# SCH_HackClub-PCB-1_2024-05-19.net
KiCad netlist of a schematic drawn in EasyEDA
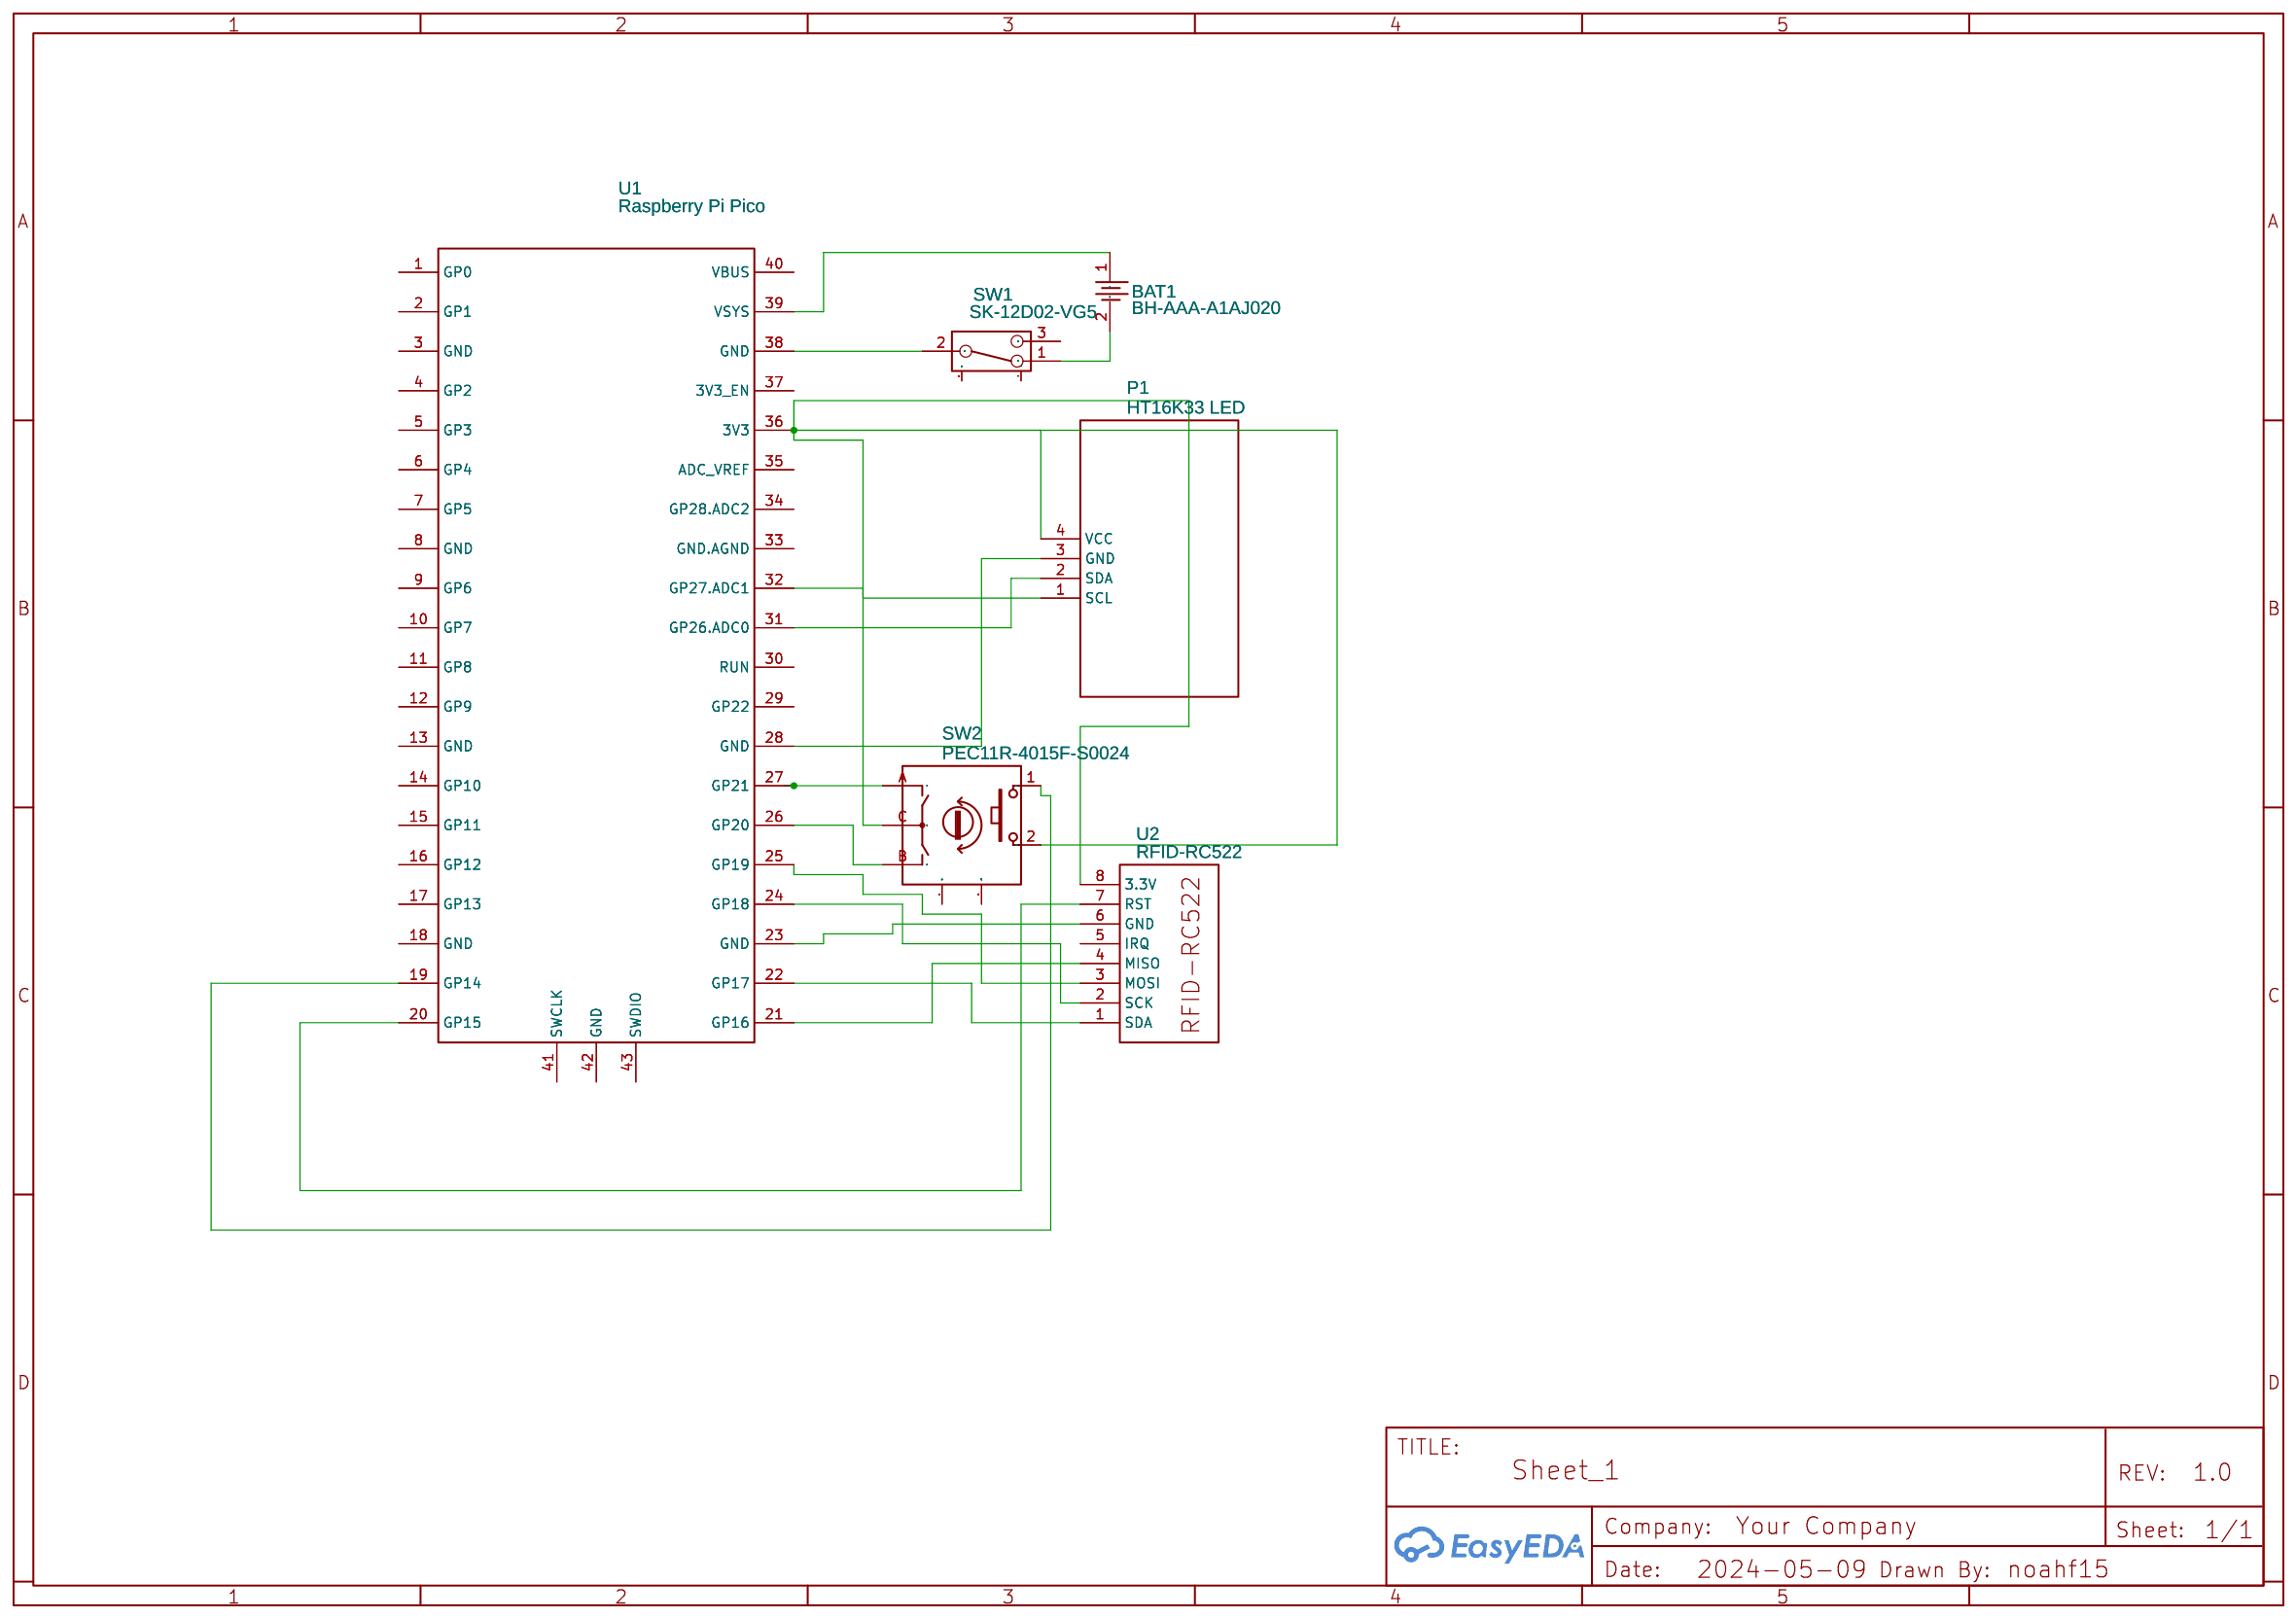
[diagram p0: schematic sheet]

(export (version "E")
  (design (tool "Eeschema 10.0.6"))
  (components
    (comp (ref "BAT1")
      (value "BH-AAA-A1AJ020")
      (fields (field (name "Manufacturer") "MYOUNG(美阳)"))
      (libsource (lib "") (part "BH-AAA-A1AJ020"))
    )
    (comp (ref "P1") (value "HT16K33 LED") (libsource (lib "") (part "HT16K33 LED")))
    (comp (ref "SW1")
      (value "SK-12D02-VG5")
      (fields (field (name "Manufacturer") "Rectangular Connectors - Contacts"))
      (libsource (lib "") (part "SK-12D02-VG5"))
    )
    (comp (ref "SW2")
      (value "PEC11R-4015F-S0024")
      (fields (field (name "Manufacturer") "BOURNS"))
      (libsource (lib "") (part "PEC11R-4015F-S0024"))
    )
    (comp (ref "U1")
      (value "Raspberry Pi Pico")
      (fields (field (name "Manufacturer") "Raspberry Pi Foundation"))
      (libsource (lib "") (part "Raspberry Pi Pico"))
    )
    (comp (ref "U2") (value "RFID-RC522") (libsource (lib "") (part "RFID-RC522")))
  )
  (nets
    (net (code "1") (name "Net-(BAT1-Pad2)") (class "Default")
      (node (ref "BAT1") (pin "2") (pinfunction "2_2") (pintype "input"))
      (node (ref "SW1") (pin "1") (pinfunction "1_1") (pintype "unspecified"))
    )
    (net (code "2") (name "Net-(P1-GND)") (class "Default")
      (node (ref "P1") (pin "3") (pinfunction "GND_3") (pintype "unspecified"))
      (node (ref "U1") (pin "28") (pinfunction "GND_28") (pintype "passive"))
    )
    (net (code "3") (name "Net-(P1-SCL)") (class "Default")
      (node (ref "P1") (pin "1") (pinfunction "SCL_1") (pintype "unspecified"))
      (node (ref "U1") (pin "32") (pinfunction "GP27.ADC1_32") (pintype "bidirectional"))
    )
    (net (code "4") (name "Net-(P1-SDA)") (class "Default")
      (node (ref "P1") (pin "2") (pinfunction "SDA_2") (pintype "unspecified"))
      (node (ref "U1") (pin "31") (pinfunction "GP26.ADC0_31") (pintype "bidirectional"))
    )
    (net (code "5") (name "Net-(P1-VCC)") (class "Default")
      (node (ref "P1") (pin "4") (pinfunction "VCC_4") (pintype "unspecified"))
      (node (ref "SW2") (pin "2") (pinfunction "2_2") (pintype "unspecified"))
      (node (ref "SW2") (pin "C") (pinfunction "C_C") (pintype "unspecified"))
      (node (ref "U1") (pin "36") (pinfunction "3V3_36") (pintype "passive"))
      (node (ref "U2") (pin "8") (pinfunction "3.3V_8") (pintype "unspecified"))
    )
    (net (code "6") (name "Net-(SW1-Pad2)") (class "Default")
      (node (ref "SW1") (pin "2") (pinfunction "2_2") (pintype "unspecified"))
      (node (ref "U1") (pin "38") (pinfunction "GND_38") (pintype "passive"))
    )
    (net (code "7") (name "Net-(U1-GP14)") (class "Default")
      (node (ref "SW2") (pin "1") (pinfunction "1_1") (pintype "unspecified"))
      (node (ref "U1") (pin "19") (pinfunction "GP14_19") (pintype "bidirectional"))
    )
    (net (code "8") (name "Net-(U1-GP15)") (class "Default")
      (node (ref "U1") (pin "20") (pinfunction "GP15_20") (pintype "bidirectional"))
      (node (ref "U2") (pin "7") (pinfunction "RST_7") (pintype "unspecified"))
    )
    (net (code "9") (name "Net-(U1-GP16)") (class "Default")
      (node (ref "U1") (pin "21") (pinfunction "GP16_21") (pintype "bidirectional"))
      (node (ref "U2") (pin "4") (pinfunction "MISO_4") (pintype "unspecified"))
    )
    (net (code "10") (name "Net-(U1-GP17)") (class "Default")
      (node (ref "U1") (pin "22") (pinfunction "GP17_22") (pintype "bidirectional"))
      (node (ref "U2") (pin "1") (pinfunction "SDA_1") (pintype "unspecified"))
    )
    (net (code "11") (name "Net-(U1-GP18)") (class "Default")
      (node (ref "U1") (pin "24") (pinfunction "GP18_24") (pintype "bidirectional"))
      (node (ref "U2") (pin "2") (pinfunction "SCK_2") (pintype "unspecified"))
    )
    (net (code "12") (name "Net-(U1-GP19)") (class "Default")
      (node (ref "U1") (pin "25") (pinfunction "GP19_25") (pintype "bidirectional"))
      (node (ref "U2") (pin "3") (pinfunction "MOSI_3") (pintype "unspecified"))
    )
    (net (code "13") (name "Net-(U1-GP20)") (class "Default")
      (node (ref "SW2") (pin "B") (pinfunction "B_B") (pintype "unspecified"))
      (node (ref "U1") (pin "26") (pinfunction "GP20_26") (pintype "bidirectional"))
    )
    (net (code "14") (name "Net-(U1-GP21)") (class "Default")
      (node (ref "SW2") (pin "A") (pinfunction "A_A") (pintype "unspecified"))
      (node (ref "U1") (pin "27") (pinfunction "GP21_27") (pintype "bidirectional"))
    )
    (net (code "15") (name "Net-(U1-VSYS)") (class "Default")
      (node (ref "BAT1") (pin "1") (pinfunction "1_1") (pintype "input"))
      (node (ref "U1") (pin "39") (pinfunction "VSYS_39") (pintype "passive"))
    )
    (net (code "16") (name "Net-(U2-GND)") (class "Default")
      (node (ref "U1") (pin "23") (pinfunction "GND_23") (pintype "passive"))
      (node (ref "U2") (pin "6") (pinfunction "GND_6") (pintype "unspecified"))
    )
    (net (code "17") (name "unconnected-(SW1-Pad3)") (class "Default")
      (node (ref "SW1") (pin "3") (pinfunction "3_3") (pintype "unspecified"))
    )
    (net (code "18") (name "unconnected-(SW1-Pad4)") (class "Default")
      (node (ref "SW1") (pin "4") (pinfunction "4_4") (pintype "unspecified"))
    )
    (net (code "19") (name "unconnected-(SW1-Pad5)") (class "Default")
      (node (ref "SW1") (pin "5") (pinfunction "5_5") (pintype "unspecified"))
    )
    (net (code "20") (name "unconnected-(SW2-PadMT1)") (class "Default")
      (node (ref "SW2") (pin "MT1") (pinfunction "MT1_MT1") (pintype "unspecified"))
    )
    (net (code "21") (name "unconnected-(SW2-PadMT2)") (class "Default")
      (node (ref "SW2") (pin "MT2") (pinfunction "MT2_MT2") (pintype "unspecified"))
    )
    (net (code "22") (name "unconnected-(U1-3V3_EN-Pad37)") (class "Default")
      (node (ref "U1") (pin "37") (pinfunction "3V3_EN_37") (pintype "input"))
    )
    (net (code "23") (name "unconnected-(U1-ADC_VREF-Pad35)") (class "Default")
      (node (ref "U1") (pin "35") (pinfunction "ADC_VREF_35") (pintype "passive"))
    )
    (net (code "24") (name "unconnected-(U1-GND-Pad3)") (class "Default")
      (node (ref "U1") (pin "3") (pinfunction "GND_3") (pintype "passive"))
    )
    (net (code "25") (name "unconnected-(U1-GND-Pad8)") (class "Default")
      (node (ref "U1") (pin "8") (pinfunction "GND_8") (pintype "passive"))
    )
    (net (code "26") (name "unconnected-(U1-GND-Pad13)") (class "Default")
      (node (ref "U1") (pin "13") (pinfunction "GND_13") (pintype "passive"))
    )
    (net (code "27") (name "unconnected-(U1-GND-Pad18)") (class "Default")
      (node (ref "U1") (pin "18") (pinfunction "GND_18") (pintype "passive"))
    )
    (net (code "28") (name "unconnected-(U1-GND-Pad42)") (class "Default")
      (node (ref "U1") (pin "42") (pinfunction "GND_42") (pintype "passive"))
    )
    (net (code "29") (name "unconnected-(U1-GND.AGND-Pad33)") (class "Default")
      (node (ref "U1") (pin "33") (pinfunction "GND.AGND_33") (pintype "passive"))
    )
    (net (code "30") (name "unconnected-(U1-GP0-Pad1)") (class "Default")
      (node (ref "U1") (pin "1") (pinfunction "GP0_1") (pintype "bidirectional"))
    )
    (net (code "31") (name "unconnected-(U1-GP1-Pad2)") (class "Default")
      (node (ref "U1") (pin "2") (pinfunction "GP1_2") (pintype "bidirectional"))
    )
    (net (code "32") (name "unconnected-(U1-GP2-Pad4)") (class "Default")
      (node (ref "U1") (pin "4") (pinfunction "GP2_4") (pintype "bidirectional"))
    )
    (net (code "33") (name "unconnected-(U1-GP3-Pad5)") (class "Default")
      (node (ref "U1") (pin "5") (pinfunction "GP3_5") (pintype "bidirectional"))
    )
    (net (code "34") (name "unconnected-(U1-GP4-Pad6)") (class "Default")
      (node (ref "U1") (pin "6") (pinfunction "GP4_6") (pintype "bidirectional"))
    )
    (net (code "35") (name "unconnected-(U1-GP5-Pad7)") (class "Default")
      (node (ref "U1") (pin "7") (pinfunction "GP5_7") (pintype "bidirectional"))
    )
    (net (code "36") (name "unconnected-(U1-GP6-Pad9)") (class "Default")
      (node (ref "U1") (pin "9") (pinfunction "GP6_9") (pintype "bidirectional"))
    )
    (net (code "37") (name "unconnected-(U1-GP7-Pad10)") (class "Default")
      (node (ref "U1") (pin "10") (pinfunction "GP7_10") (pintype "bidirectional"))
    )
    (net (code "38") (name "unconnected-(U1-GP8-Pad11)") (class "Default")
      (node (ref "U1") (pin "11") (pinfunction "GP8_11") (pintype "bidirectional"))
    )
    (net (code "39") (name "unconnected-(U1-GP9-Pad12)") (class "Default")
      (node (ref "U1") (pin "12") (pinfunction "GP9_12") (pintype "bidirectional"))
    )
    (net (code "40") (name "unconnected-(U1-GP10-Pad14)") (class "Default")
      (node (ref "U1") (pin "14") (pinfunction "GP10_14") (pintype "bidirectional"))
    )
    (net (code "41") (name "unconnected-(U1-GP11-Pad15)") (class "Default")
      (node (ref "U1") (pin "15") (pinfunction "GP11_15") (pintype "bidirectional"))
    )
    (net (code "42") (name "unconnected-(U1-GP12-Pad16)") (class "Default")
      (node (ref "U1") (pin "16") (pinfunction "GP12_16") (pintype "bidirectional"))
    )
    (net (code "43") (name "unconnected-(U1-GP13-Pad17)") (class "Default")
      (node (ref "U1") (pin "17") (pinfunction "GP13_17") (pintype "bidirectional"))
    )
    (net (code "44") (name "unconnected-(U1-GP22-Pad29)") (class "Default")
      (node (ref "U1") (pin "29") (pinfunction "GP22_29") (pintype "bidirectional"))
    )
    (net (code "45") (name "unconnected-(U1-GP28.ADC2-Pad34)") (class "Default")
      (node (ref "U1") (pin "34") (pinfunction "GP28.ADC2_34") (pintype "bidirectional"))
    )
    (net (code "46") (name "unconnected-(U1-RUN-Pad30)") (class "Default")
      (node (ref "U1") (pin "30") (pinfunction "RUN_30") (pintype "unspecified"))
    )
    (net (code "47") (name "unconnected-(U1-SWCLK-Pad41)") (class "Default")
      (node (ref "U1") (pin "41") (pinfunction "SWCLK_41") (pintype "bidirectional"))
    )
    (net (code "48") (name "unconnected-(U1-SWDIO-Pad43)") (class "Default")
      (node (ref "U1") (pin "43") (pinfunction "SWDIO_43") (pintype "bidirectional"))
    )
    (net (code "49") (name "unconnected-(U1-VBUS-Pad40)") (class "Default")
      (node (ref "U1") (pin "40") (pinfunction "VBUS_40") (pintype "passive"))
    )
    (net (code "50") (name "unconnected-(U2-IRQ-Pad5)") (class "Default")
      (node (ref "U2") (pin "5") (pinfunction "IRQ_5") (pintype "unspecified"))
    )
  )
)
